# power_hub.net
KiCad netlist of a schematic drawn in EAGLE
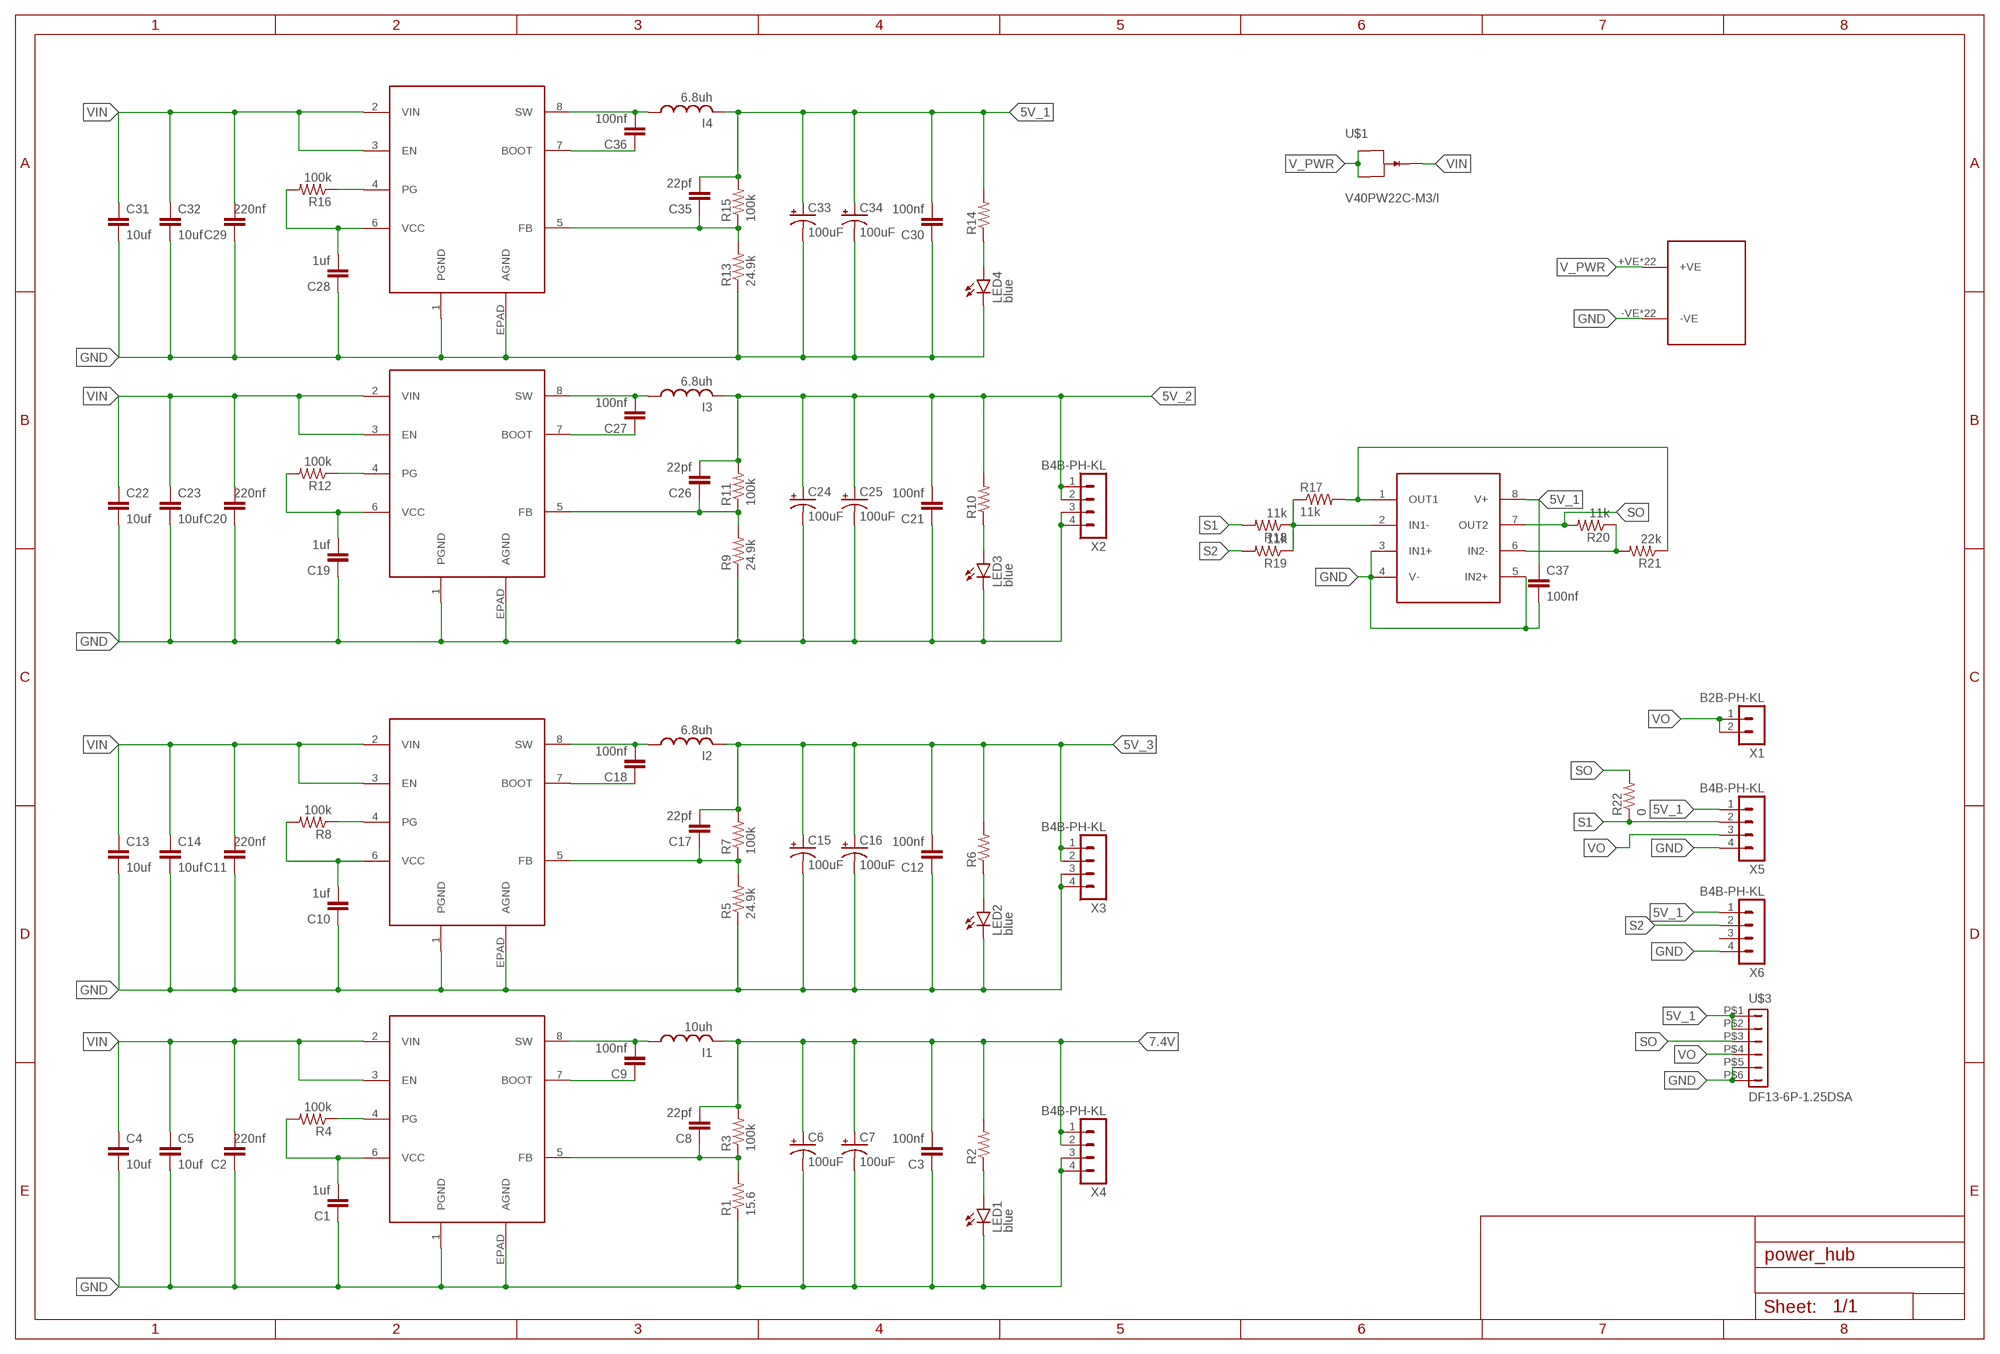
[diagram p0: schematic, sheet 1]

(export (version "E")
  (design (tool "Eeschema 10.0.6"))
  (components
    (comp (ref "C1")
      (value "1uf")
      (footprint "eagle-import:C0805")
      (libsource (lib "eagle-import") (part "C-EUC0805"))
    )
    (comp (ref "C2")
      (value "220nf")
      (footprint "eagle-import:C0805")
      (libsource (lib "eagle-import") (part "C-EUC0805"))
    )
    (comp (ref "C3")
      (value "100nf")
      (footprint "eagle-import:C0805")
      (libsource (lib "eagle-import") (part "C-EUC0805"))
    )
    (comp (ref "C4")
      (value "10uf")
      (footprint "eagle-import:C1210")
      (libsource (lib "eagle-import") (part "C-EUC1210"))
    )
    (comp (ref "C5")
      (value "10uf")
      (footprint "eagle-import:C1210")
      (libsource (lib "eagle-import") (part "C-EUC1210"))
    )
    (comp (ref "C6")
      (value "100uF")
      (footprint "eagle-import:PANASONIC_D")
      (libsource (lib "eagle-import") (part "100UF-POLAR-25V-20%(ELEC)"))
    )
    (comp (ref "C7")
      (value "100uF")
      (footprint "eagle-import:PANASONIC_D")
      (libsource (lib "eagle-import") (part "100UF-POLAR-25V-20%(ELEC)"))
    )
    (comp (ref "C8")
      (value "22pf")
      (footprint "eagle-import:C0805")
      (libsource (lib "eagle-import") (part "C-EUC0805"))
    )
    (comp (ref "C9")
      (value "100nf")
      (footprint "eagle-import:C0805")
      (libsource (lib "eagle-import") (part "C-EUC0805"))
    )
    (comp (ref "C10")
      (value "1uf")
      (footprint "eagle-import:C0805")
      (libsource (lib "eagle-import") (part "C-EUC0805"))
    )
    (comp (ref "C11")
      (value "220nf")
      (footprint "eagle-import:C0805")
      (libsource (lib "eagle-import") (part "C-EUC0805"))
    )
    (comp (ref "C12")
      (value "100nf")
      (footprint "eagle-import:C0805")
      (libsource (lib "eagle-import") (part "C-EUC0805"))
    )
    (comp (ref "C13")
      (value "10uf")
      (footprint "eagle-import:C1210")
      (libsource (lib "eagle-import") (part "C-EUC1210"))
    )
    (comp (ref "C14")
      (value "10uf")
      (footprint "eagle-import:C1210")
      (libsource (lib "eagle-import") (part "C-EUC1210"))
    )
    (comp (ref "C15")
      (value "100uF")
      (footprint "eagle-import:PANASONIC_D")
      (libsource (lib "eagle-import") (part "100UF-POLAR-25V-20%(ELEC)"))
    )
    (comp (ref "C16")
      (value "100uF")
      (footprint "eagle-import:PANASONIC_D")
      (libsource (lib "eagle-import") (part "100UF-POLAR-25V-20%(ELEC)"))
    )
    (comp (ref "C17")
      (value "22pf")
      (footprint "eagle-import:C0805")
      (libsource (lib "eagle-import") (part "C-EUC0805"))
    )
    (comp (ref "C18")
      (value "100nf")
      (footprint "eagle-import:C0805")
      (libsource (lib "eagle-import") (part "C-EUC0805"))
    )
    (comp (ref "C19")
      (value "1uf")
      (footprint "eagle-import:C0805")
      (libsource (lib "eagle-import") (part "C-EUC0805"))
    )
    (comp (ref "C20")
      (value "220nf")
      (footprint "eagle-import:C0805")
      (libsource (lib "eagle-import") (part "C-EUC0805"))
    )
    (comp (ref "C21")
      (value "100nf")
      (footprint "eagle-import:C0805")
      (libsource (lib "eagle-import") (part "C-EUC0805"))
    )
    (comp (ref "C22")
      (value "10uf")
      (footprint "eagle-import:C1210")
      (libsource (lib "eagle-import") (part "C-EUC1210"))
    )
    (comp (ref "C23")
      (value "10uf")
      (footprint "eagle-import:C1210")
      (libsource (lib "eagle-import") (part "C-EUC1210"))
    )
    (comp (ref "C24")
      (value "100uF")
      (footprint "eagle-import:PANASONIC_D")
      (libsource (lib "eagle-import") (part "100UF-POLAR-25V-20%(ELEC)"))
    )
    (comp (ref "C25")
      (value "100uF")
      (footprint "eagle-import:PANASONIC_D")
      (libsource (lib "eagle-import") (part "100UF-POLAR-25V-20%(ELEC)"))
    )
    (comp (ref "C26")
      (value "22pf")
      (footprint "eagle-import:C0805")
      (libsource (lib "eagle-import") (part "C-EUC0805"))
    )
    (comp (ref "C27")
      (value "100nf")
      (footprint "eagle-import:C0805")
      (libsource (lib "eagle-import") (part "C-EUC0805"))
    )
    (comp (ref "C28")
      (value "1uf")
      (footprint "eagle-import:C0805")
      (libsource (lib "eagle-import") (part "C-EUC0805"))
    )
    (comp (ref "C29")
      (value "220nf")
      (footprint "eagle-import:C0805")
      (libsource (lib "eagle-import") (part "C-EUC0805"))
    )
    (comp (ref "C30")
      (value "100nf")
      (footprint "eagle-import:C0805")
      (libsource (lib "eagle-import") (part "C-EUC0805"))
    )
    (comp (ref "C31")
      (value "10uf")
      (footprint "eagle-import:C1210")
      (libsource (lib "eagle-import") (part "C-EUC1210"))
    )
    (comp (ref "C32")
      (value "10uf")
      (footprint "eagle-import:C1210")
      (libsource (lib "eagle-import") (part "C-EUC1210"))
    )
    (comp (ref "C33")
      (value "100uF")
      (footprint "eagle-import:PANASONIC_D")
      (libsource (lib "eagle-import") (part "100UF-POLAR-25V-20%(ELEC)"))
    )
    (comp (ref "C34")
      (value "100uF")
      (footprint "eagle-import:PANASONIC_D")
      (libsource (lib "eagle-import") (part "100UF-POLAR-25V-20%(ELEC)"))
    )
    (comp (ref "C35")
      (value "22pf")
      (footprint "eagle-import:C0805")
      (libsource (lib "eagle-import") (part "C-EUC0805"))
    )
    (comp (ref "C36")
      (value "100nf")
      (footprint "eagle-import:C0805")
      (libsource (lib "eagle-import") (part "C-EUC0805"))
    )
    (comp (ref "C37")
      (value "100nf")
      (footprint "eagle-import:C0805")
      (libsource (lib "eagle-import") (part "C-EUC0805"))
    )
    (comp (ref "I1")
      (value "10uh")
      (footprint "eagle-import:INDUCTOR-1265")
      (libsource (lib "eagle-import") (part "INDUCTORINDUCTOR-1265"))
    )
    (comp (ref "I2")
      (value "6.8uh")
      (footprint "eagle-import:INDUCTOR-1265")
      (libsource (lib "eagle-import") (part "INDUCTORINDUCTOR-1265"))
    )
    (comp (ref "I3")
      (value "6.8uh")
      (footprint "eagle-import:INDUCTOR-1265")
      (libsource (lib "eagle-import") (part "INDUCTORINDUCTOR-1265"))
    )
    (comp (ref "I4")
      (value "6.8uh")
      (footprint "eagle-import:INDUCTOR-1265")
      (libsource (lib "eagle-import") (part "INDUCTORINDUCTOR-1265"))
    )
    (comp (ref "LED1")
      (value "blue")
      (footprint "eagle-import:CHIPLED_0805")
      (libsource (lib "eagle-import") (part "LEDCHIPLED_0805"))
    )
    (comp (ref "LED2")
      (value "blue")
      (footprint "eagle-import:CHIPLED_0805")
      (libsource (lib "eagle-import") (part "LEDCHIPLED_0805"))
    )
    (comp (ref "LED3")
      (value "blue")
      (footprint "eagle-import:CHIPLED_0805")
      (libsource (lib "eagle-import") (part "LEDCHIPLED_0805"))
    )
    (comp (ref "LED4")
      (value "blue")
      (footprint "eagle-import:CHIPLED_0805")
      (libsource (lib "eagle-import") (part "LEDCHIPLED_0805"))
    )
    (comp (ref "R1")
      (value "15.6")
      (footprint "eagle-import:R0805")
      (libsource (lib "eagle-import") (part "R-US_R0805"))
    )
    (comp (ref "R2")
      (value "1k")
      (footprint "eagle-import:R0805")
      (libsource (lib "eagle-import") (part "R-US_R0805"))
    )
    (comp (ref "R3")
      (value "100k")
      (footprint "eagle-import:R0805")
      (libsource (lib "eagle-import") (part "R-US_R0805"))
    )
    (comp (ref "R4")
      (value "100k")
      (footprint "eagle-import:R0805")
      (libsource (lib "eagle-import") (part "R-US_R0805"))
    )
    (comp (ref "R5")
      (value "24.9k")
      (footprint "eagle-import:R0805")
      (libsource (lib "eagle-import") (part "R-US_R0805"))
    )
    (comp (ref "R6")
      (value "1k")
      (footprint "eagle-import:R0805")
      (libsource (lib "eagle-import") (part "R-US_R0805"))
    )
    (comp (ref "R7")
      (value "100k")
      (footprint "eagle-import:R0805")
      (libsource (lib "eagle-import") (part "R-US_R0805"))
    )
    (comp (ref "R8")
      (value "100k")
      (footprint "eagle-import:R0805")
      (libsource (lib "eagle-import") (part "R-US_R0805"))
    )
    (comp (ref "R9")
      (value "24.9k")
      (footprint "eagle-import:R0805")
      (libsource (lib "eagle-import") (part "R-US_R0805"))
    )
    (comp (ref "R10")
      (value "1k")
      (footprint "eagle-import:R0805")
      (libsource (lib "eagle-import") (part "R-US_R0805"))
    )
    (comp (ref "R11")
      (value "100k")
      (footprint "eagle-import:R0805")
      (libsource (lib "eagle-import") (part "R-US_R0805"))
    )
    (comp (ref "R12")
      (value "100k")
      (footprint "eagle-import:R0805")
      (libsource (lib "eagle-import") (part "R-US_R0805"))
    )
    (comp (ref "R13")
      (value "24.9k")
      (footprint "eagle-import:R0805")
      (libsource (lib "eagle-import") (part "R-US_R0805"))
    )
    (comp (ref "R14")
      (value "1k")
      (footprint "eagle-import:R0805")
      (libsource (lib "eagle-import") (part "R-US_R0805"))
    )
    (comp (ref "R15")
      (value "100k")
      (footprint "eagle-import:R0805")
      (libsource (lib "eagle-import") (part "R-US_R0805"))
    )
    (comp (ref "R16")
      (value "100k")
      (footprint "eagle-import:R0805")
      (libsource (lib "eagle-import") (part "R-US_R0805"))
    )
    (comp (ref "R17")
      (value "11k")
      (footprint "eagle-import:R0805")
      (libsource (lib "eagle-import") (part "R-US_R0805"))
    )
    (comp (ref "R18")
      (value "11k")
      (footprint "eagle-import:R0805")
      (libsource (lib "eagle-import") (part "R-US_R0805"))
    )
    (comp (ref "R19")
      (value "11k")
      (footprint "eagle-import:R0805")
      (libsource (lib "eagle-import") (part "R-US_R0805"))
    )
    (comp (ref "R20")
      (value "11k")
      (footprint "eagle-import:R0805")
      (libsource (lib "eagle-import") (part "R-US_R0805"))
    )
    (comp (ref "R21")
      (value "22k")
      (footprint "eagle-import:R0805")
      (libsource (lib "eagle-import") (part "R-US_R0805"))
    )
    (comp (ref "R22")
      (value "0")
      (footprint "eagle-import:R0805")
      (libsource (lib "eagle-import") (part "R-US_R0805"))
    )
    (comp (ref "U$1")
      (value "V40PW22C-M3/I")
      (footprint "eagle-import:TO-252AE")
      (libsource (lib "eagle-import") (part "DIODE-TO252"))
    )
    (comp (ref "U$2")
      (value "LM3588")
      (footprint "eagle-import:SOP-08")
      (libsource (lib "eagle-import") (part "LM3588"))
    )
    (comp (ref "U$3")
      (value "DF13-6P-1.25DSA")
      (footprint "eagle-import:DF13-6P-1.25DSA")
      (libsource (lib "eagle-import") (part "DF13-6P-1.25DSA"))
    )
    (comp (ref "U$4")
      (value "CON_PAD")
      (footprint "eagle-import:MOTOR_PAD")
      (libsource (lib "eagle-import") (part "CON_PAD"))
    )
    (comp (ref "U1")
      (value "LMR33640")
      (footprint "eagle-import:SO-POWERPAD8_DDA_TEX-M")
      (libsource (lib "eagle-import") (part "LMR33640"))
    )
    (comp (ref "U2")
      (value "LMR33640")
      (footprint "eagle-import:SO-POWERPAD8_DDA_TEX-M")
      (libsource (lib "eagle-import") (part "LMR33640"))
    )
    (comp (ref "U3")
      (value "LMR33640")
      (footprint "eagle-import:SO-POWERPAD8_DDA_TEX-M")
      (libsource (lib "eagle-import") (part "LMR33640"))
    )
    (comp (ref "U4")
      (value "LMR33640")
      (footprint "eagle-import:SO-POWERPAD8_DDA_TEX-M")
      (libsource (lib "eagle-import") (part "LMR33640"))
    )
    (comp (ref "X1")
      (value "B2B-PH-KL")
      (footprint "eagle-import:B2B-PH-K-S")
      (libsource (lib "eagle-import") (part "B2B-PH-KL"))
    )
    (comp (ref "X2")
      (value "B4B-PH-KL")
      (footprint "eagle-import:B4B-PH-K-S")
      (libsource (lib "eagle-import") (part "B4B-PH-KL"))
    )
    (comp (ref "X3")
      (value "B4B-PH-KL")
      (footprint "eagle-import:B4B-PH-K-S")
      (libsource (lib "eagle-import") (part "B4B-PH-KL"))
    )
    (comp (ref "X4")
      (value "B4B-PH-KL")
      (footprint "eagle-import:B4B-PH-K-S")
      (libsource (lib "eagle-import") (part "B4B-PH-KL"))
    )
    (comp (ref "X5")
      (value "B4B-PH-KL")
      (footprint "eagle-import:B4B-PH-K-S")
      (libsource (lib "eagle-import") (part "B4B-PH-KL"))
    )
    (comp (ref "X6")
      (value "B4B-PH-KL")
      (footprint "eagle-import:B4B-PH-K-S")
      (libsource (lib "eagle-import") (part "B4B-PH-KL"))
    )
  )
  (nets
    (net (code "1") (name "5V_1") (class "Default")
      (node (ref "C30") (pin "2") (pinfunction "2_2") (pintype "passive"))
      (node (ref "C33") (pin "+") (pinfunction "+_+") (pintype "passive"))
      (node (ref "C34") (pin "+") (pinfunction "+_+") (pintype "passive"))
      (node (ref "C35") (pin "2") (pinfunction "2_2") (pintype "passive"))
      (node (ref "C37") (pin "1") (pinfunction "1_1") (pintype "passive"))
      (node (ref "I4") (pin "P$2") (pinfunction "2_P$2") (pintype "passive"))
      (node (ref "R14") (pin "2") (pinfunction "2_2") (pintype "passive"))
      (node (ref "R15") (pin "2") (pinfunction "2_2") (pintype "passive"))
      (node (ref "U$2") (pin "8") (pinfunction "V+_8") (pintype "bidirectional"))
      (node (ref "U$3") (pin "P$1") (pinfunction "1_P$1") (pintype "passive"))
      (node (ref "U$3") (pin "P$2") (pinfunction "2_P$2") (pintype "passive"))
      (node (ref "X5") (pin "1") (pinfunction "1_1") (pintype "passive"))
      (node (ref "X6") (pin "1") (pinfunction "1_1") (pintype "passive"))
    )
    (net (code "2") (name "5V_2") (class "Default")
      (node (ref "C21") (pin "2") (pinfunction "2_2") (pintype "passive"))
      (node (ref "C24") (pin "+") (pinfunction "+_+") (pintype "passive"))
      (node (ref "C25") (pin "+") (pinfunction "+_+") (pintype "passive"))
      (node (ref "C26") (pin "2") (pinfunction "2_2") (pintype "passive"))
      (node (ref "I3") (pin "P$2") (pinfunction "2_P$2") (pintype "passive"))
      (node (ref "R10") (pin "2") (pinfunction "2_2") (pintype "passive"))
      (node (ref "R11") (pin "2") (pinfunction "2_2") (pintype "passive"))
      (node (ref "X2") (pin "1") (pinfunction "1_1") (pintype "passive"))
      (node (ref "X2") (pin "2") (pinfunction "2_2") (pintype "passive"))
    )
    (net (code "3") (name "5V_3") (class "Default")
      (node (ref "C12") (pin "2") (pinfunction "2_2") (pintype "passive"))
      (node (ref "C15") (pin "+") (pinfunction "+_+") (pintype "passive"))
      (node (ref "C16") (pin "+") (pinfunction "+_+") (pintype "passive"))
      (node (ref "C17") (pin "2") (pinfunction "2_2") (pintype "passive"))
      (node (ref "I2") (pin "P$2") (pinfunction "2_P$2") (pintype "passive"))
      (node (ref "R6") (pin "2") (pinfunction "2_2") (pintype "passive"))
      (node (ref "R7") (pin "2") (pinfunction "2_2") (pintype "passive"))
      (node (ref "X3") (pin "1") (pinfunction "1_1") (pintype "passive"))
      (node (ref "X3") (pin "2") (pinfunction "2_2") (pintype "passive"))
    )
    (net (code "4") (name "7.4V") (class "Default")
      (node (ref "C3") (pin "2") (pinfunction "2_2") (pintype "passive"))
      (node (ref "C6") (pin "+") (pinfunction "+_+") (pintype "passive"))
      (node (ref "C7") (pin "+") (pinfunction "+_+") (pintype "passive"))
      (node (ref "C8") (pin "2") (pinfunction "2_2") (pintype "passive"))
      (node (ref "I1") (pin "P$2") (pinfunction "2_P$2") (pintype "passive"))
      (node (ref "R2") (pin "2") (pinfunction "2_2") (pintype "passive"))
      (node (ref "R3") (pin "2") (pinfunction "2_2") (pintype "passive"))
      (node (ref "X4") (pin "1") (pinfunction "1_1") (pintype "passive"))
      (node (ref "X4") (pin "2") (pinfunction "2_2") (pintype "passive"))
    )
    (net (code "5") (name "GND") (class "Default")
      (node (ref "C1") (pin "1") (pinfunction "1_1") (pintype "passive"))
      (node (ref "C10") (pin "1") (pinfunction "1_1") (pintype "passive"))
      (node (ref "C11") (pin "1") (pinfunction "1_1") (pintype "passive"))
      (node (ref "C12") (pin "1") (pinfunction "1_1") (pintype "passive"))
      (node (ref "C13") (pin "2") (pinfunction "2_2") (pintype "passive"))
      (node (ref "C14") (pin "2") (pinfunction "2_2") (pintype "passive"))
      (node (ref "C15") (pin "-") (pinfunction "-_-") (pintype "passive"))
      (node (ref "C16") (pin "-") (pinfunction "-_-") (pintype "passive"))
      (node (ref "C19") (pin "1") (pinfunction "1_1") (pintype "passive"))
      (node (ref "C2") (pin "1") (pinfunction "1_1") (pintype "passive"))
      (node (ref "C20") (pin "1") (pinfunction "1_1") (pintype "passive"))
      (node (ref "C21") (pin "1") (pinfunction "1_1") (pintype "passive"))
      (node (ref "C22") (pin "2") (pinfunction "2_2") (pintype "passive"))
      (node (ref "C23") (pin "2") (pinfunction "2_2") (pintype "passive"))
      (node (ref "C24") (pin "-") (pinfunction "-_-") (pintype "passive"))
      (node (ref "C25") (pin "-") (pinfunction "-_-") (pintype "passive"))
      (node (ref "C28") (pin "1") (pinfunction "1_1") (pintype "passive"))
      (node (ref "C29") (pin "1") (pinfunction "1_1") (pintype "passive"))
      (node (ref "C3") (pin "1") (pinfunction "1_1") (pintype "passive"))
      (node (ref "C30") (pin "1") (pinfunction "1_1") (pintype "passive"))
      (node (ref "C31") (pin "2") (pinfunction "2_2") (pintype "passive"))
      (node (ref "C32") (pin "2") (pinfunction "2_2") (pintype "passive"))
      (node (ref "C33") (pin "-") (pinfunction "-_-") (pintype "passive"))
      (node (ref "C34") (pin "-") (pinfunction "-_-") (pintype "passive"))
      (node (ref "C37") (pin "2") (pinfunction "2_2") (pintype "passive"))
      (node (ref "C4") (pin "2") (pinfunction "2_2") (pintype "passive"))
      (node (ref "C5") (pin "2") (pinfunction "2_2") (pintype "passive"))
      (node (ref "C6") (pin "-") (pinfunction "-_-") (pintype "passive"))
      (node (ref "C7") (pin "-") (pinfunction "-_-") (pintype "passive"))
      (node (ref "LED1") (pin "C") (pinfunction "C_C") (pintype "passive"))
      (node (ref "LED2") (pin "C") (pinfunction "C_C") (pintype "passive"))
      (node (ref "LED3") (pin "C") (pinfunction "C_C") (pintype "passive"))
      (node (ref "LED4") (pin "C") (pinfunction "C_C") (pintype "passive"))
      (node (ref "R1") (pin "1") (pinfunction "1_1") (pintype "passive"))
      (node (ref "R13") (pin "1") (pinfunction "1_1") (pintype "passive"))
      (node (ref "R5") (pin "1") (pinfunction "1_1") (pintype "passive"))
      (node (ref "R9") (pin "1") (pinfunction "1_1") (pintype "passive"))
      (node (ref "U$2") (pin "3") (pinfunction "IN1+_3") (pintype "bidirectional"))
      (node (ref "U$2") (pin "4") (pinfunction "V-_4") (pintype "bidirectional"))
      (node (ref "U$2") (pin "5") (pinfunction "IN2+_5") (pintype "bidirectional"))
      (node (ref "U$3") (pin "P$5") (pinfunction "5_P$5") (pintype "passive"))
      (node (ref "U$3") (pin "P$6") (pinfunction "6_P$6") (pintype "passive"))
      (node (ref "U$4") (pin "-VE") (pinfunction "-VE_-VE") (pintype "output"))
      (node (ref "U$4") (pin "-VE_1") (pinfunction "-VE_-VE_1") (pintype "output"))
      (node (ref "U$4") (pin "V37") (pinfunction "-VE_V37") (pintype "output"))
      (node (ref "U$4") (pin "V38") (pinfunction "-VE_V38") (pintype "output"))
      (node (ref "U$4") (pin "V39") (pinfunction "-VE_V39") (pintype "output"))
      (node (ref "U$4") (pin "V40") (pinfunction "-VE_V40") (pintype "output"))
      (node (ref "U$4") (pin "V41") (pinfunction "-VE_V41") (pintype "output"))
      (node (ref "U$4") (pin "V42") (pinfunction "-VE_V42") (pintype "output"))
      (node (ref "U$4") (pin "V43") (pinfunction "-VE_V43") (pintype "output"))
      (node (ref "U$4") (pin "V44") (pinfunction "-VE_V44") (pintype "output"))
      (node (ref "U$4") (pin "V45") (pinfunction "-VE_V45") (pintype "output"))
      (node (ref "U$4") (pin "V46") (pinfunction "-VE_V46") (pintype "output"))
      (node (ref "U$4") (pin "V47") (pinfunction "-VE_V47") (pintype "output"))
      (node (ref "U$4") (pin "V48") (pinfunction "-VE_V48") (pintype "output"))
      (node (ref "U$4") (pin "V49") (pinfunction "-VE_V49") (pintype "output"))
      (node (ref "U$4") (pin "V50") (pinfunction "-VE_V50") (pintype "output"))
      (node (ref "U$4") (pin "V51") (pinfunction "-VE_V51") (pintype "output"))
      (node (ref "U$4") (pin "V52") (pinfunction "-VE_V52") (pintype "output"))
      (node (ref "U$4") (pin "V53") (pinfunction "-VE_V53") (pintype "output"))
      (node (ref "U$4") (pin "V54") (pinfunction "-VE_V54") (pintype "output"))
      (node (ref "U$4") (pin "V55") (pinfunction "-VE_V55") (pintype "output"))
      (node (ref "U$4") (pin "V56") (pinfunction "-VE_V56") (pintype "output"))
      (node (ref "U1") (pin "1") (pinfunction "PGND_1") (pintype "bidirectional"))
      (node (ref "U1") (pin "EPAD") (pinfunction "AGND_EPAD") (pintype "bidirectional"))
      (node (ref "U2") (pin "1") (pinfunction "PGND_1") (pintype "bidirectional"))
      (node (ref "U2") (pin "EPAD") (pinfunction "AGND_EPAD") (pintype "bidirectional"))
      (node (ref "U3") (pin "1") (pinfunction "PGND_1") (pintype "bidirectional"))
      (node (ref "U3") (pin "EPAD") (pinfunction "AGND_EPAD") (pintype "bidirectional"))
      (node (ref "U4") (pin "1") (pinfunction "PGND_1") (pintype "bidirectional"))
      (node (ref "U4") (pin "EPAD") (pinfunction "AGND_EPAD") (pintype "bidirectional"))
      (node (ref "X2") (pin "3") (pinfunction "3_3") (pintype "passive"))
      (node (ref "X2") (pin "4") (pinfunction "4_4") (pintype "passive"))
      (node (ref "X3") (pin "3") (pinfunction "3_3") (pintype "passive"))
      (node (ref "X3") (pin "4") (pinfunction "4_4") (pintype "passive"))
      (node (ref "X4") (pin "3") (pinfunction "3_3") (pintype "passive"))
      (node (ref "X4") (pin "4") (pinfunction "4_4") (pintype "passive"))
      (node (ref "X5") (pin "4") (pinfunction "4_4") (pintype "passive"))
      (node (ref "X6") (pin "4") (pinfunction "4_4") (pintype "passive"))
    )
    (net (code "6") (name "Net-(I1-1)") (class "Default")
      (node (ref "C9") (pin "2") (pinfunction "2_2") (pintype "passive"))
      (node (ref "I1") (pin "P$1") (pinfunction "1_P$1") (pintype "passive"))
      (node (ref "U1") (pin "8") (pinfunction "SW_8") (pintype "bidirectional"))
    )
    (net (code "7") (name "Net-(I2-1)") (class "Default")
      (node (ref "C18") (pin "2") (pinfunction "2_2") (pintype "passive"))
      (node (ref "I2") (pin "P$1") (pinfunction "1_P$1") (pintype "passive"))
      (node (ref "U2") (pin "8") (pinfunction "SW_8") (pintype "bidirectional"))
    )
    (net (code "8") (name "Net-(I3-1)") (class "Default")
      (node (ref "C27") (pin "2") (pinfunction "2_2") (pintype "passive"))
      (node (ref "I3") (pin "P$1") (pinfunction "1_P$1") (pintype "passive"))
      (node (ref "U3") (pin "8") (pinfunction "SW_8") (pintype "bidirectional"))
    )
    (net (code "9") (name "Net-(I4-1)") (class "Default")
      (node (ref "C36") (pin "2") (pinfunction "2_2") (pintype "passive"))
      (node (ref "I4") (pin "P$1") (pinfunction "1_P$1") (pintype "passive"))
      (node (ref "U4") (pin "8") (pinfunction "SW_8") (pintype "bidirectional"))
    )
    (net (code "10") (name "Net-(LED1-PadA)") (class "Default")
      (node (ref "LED1") (pin "A") (pinfunction "A_A") (pintype "passive"))
      (node (ref "R2") (pin "1") (pinfunction "1_1") (pintype "passive"))
    )
    (net (code "11") (name "Net-(LED2-PadA)") (class "Default")
      (node (ref "LED2") (pin "A") (pinfunction "A_A") (pintype "passive"))
      (node (ref "R6") (pin "1") (pinfunction "1_1") (pintype "passive"))
    )
    (net (code "12") (name "Net-(LED3-PadA)") (class "Default")
      (node (ref "LED3") (pin "A") (pinfunction "A_A") (pintype "passive"))
      (node (ref "R10") (pin "1") (pinfunction "1_1") (pintype "passive"))
    )
    (net (code "13") (name "Net-(LED4-PadA)") (class "Default")
      (node (ref "LED4") (pin "A") (pinfunction "A_A") (pintype "passive"))
      (node (ref "R14") (pin "1") (pinfunction "1_1") (pintype "passive"))
    )
    (net (code "14") (name "Net-(U$2-IN1-)") (class "Default")
      (node (ref "R17") (pin "1") (pinfunction "1_1") (pintype "passive"))
      (node (ref "R18") (pin "1") (pinfunction "1_1") (pintype "passive"))
      (node (ref "R19") (pin "1") (pinfunction "1_1") (pintype "passive"))
      (node (ref "U$2") (pin "2") (pinfunction "IN1-_2") (pintype "bidirectional"))
    )
    (net (code "15") (name "Net-(U$2-IN2-)") (class "Default")
      (node (ref "R20") (pin "1") (pinfunction "1_1") (pintype "passive"))
      (node (ref "R21") (pin "2") (pinfunction "2_2") (pintype "passive"))
      (node (ref "U$2") (pin "6") (pinfunction "IN2-_6") (pintype "bidirectional"))
    )
    (net (code "16") (name "Net-(U$2-OUT1)") (class "Default")
      (node (ref "R17") (pin "2") (pinfunction "2_2") (pintype "passive"))
      (node (ref "R21") (pin "1") (pinfunction "1_1") (pintype "passive"))
      (node (ref "U$2") (pin "1") (pinfunction "OUT1_1") (pintype "bidirectional"))
    )
    (net (code "17") (name "Net-(U1-BOOT)") (class "Default")
      (node (ref "C9") (pin "1") (pinfunction "1_1") (pintype "passive"))
      (node (ref "U1") (pin "7") (pinfunction "BOOT_7") (pintype "bidirectional"))
    )
    (net (code "18") (name "Net-(U1-FB)") (class "Default")
      (node (ref "C8") (pin "1") (pinfunction "1_1") (pintype "passive"))
      (node (ref "R1") (pin "2") (pinfunction "2_2") (pintype "passive"))
      (node (ref "R3") (pin "1") (pinfunction "1_1") (pintype "passive"))
      (node (ref "U1") (pin "5") (pinfunction "FB_5") (pintype "bidirectional"))
    )
    (net (code "19") (name "Net-(U1-PG)") (class "Default")
      (node (ref "R4") (pin "1") (pinfunction "1_1") (pintype "passive"))
      (node (ref "U1") (pin "4") (pinfunction "PG_4") (pintype "bidirectional"))
    )
    (net (code "20") (name "Net-(U1-VCC)") (class "Default")
      (node (ref "C1") (pin "2") (pinfunction "2_2") (pintype "passive"))
      (node (ref "R4") (pin "2") (pinfunction "2_2") (pintype "passive"))
      (node (ref "U1") (pin "6") (pinfunction "VCC_6") (pintype "bidirectional"))
    )
    (net (code "21") (name "Net-(U2-BOOT)") (class "Default")
      (node (ref "C18") (pin "1") (pinfunction "1_1") (pintype "passive"))
      (node (ref "U2") (pin "7") (pinfunction "BOOT_7") (pintype "bidirectional"))
    )
    (net (code "22") (name "Net-(U2-FB)") (class "Default")
      (node (ref "C17") (pin "1") (pinfunction "1_1") (pintype "passive"))
      (node (ref "R5") (pin "2") (pinfunction "2_2") (pintype "passive"))
      (node (ref "R7") (pin "1") (pinfunction "1_1") (pintype "passive"))
      (node (ref "U2") (pin "5") (pinfunction "FB_5") (pintype "bidirectional"))
    )
    (net (code "23") (name "Net-(U2-PG)") (class "Default")
      (node (ref "R8") (pin "1") (pinfunction "1_1") (pintype "passive"))
      (node (ref "U2") (pin "4") (pinfunction "PG_4") (pintype "bidirectional"))
    )
    (net (code "24") (name "Net-(U2-VCC)") (class "Default")
      (node (ref "C10") (pin "2") (pinfunction "2_2") (pintype "passive"))
      (node (ref "R8") (pin "2") (pinfunction "2_2") (pintype "passive"))
      (node (ref "U2") (pin "6") (pinfunction "VCC_6") (pintype "bidirectional"))
    )
    (net (code "25") (name "Net-(U3-BOOT)") (class "Default")
      (node (ref "C27") (pin "1") (pinfunction "1_1") (pintype "passive"))
      (node (ref "U3") (pin "7") (pinfunction "BOOT_7") (pintype "bidirectional"))
    )
    (net (code "26") (name "Net-(U3-FB)") (class "Default")
      (node (ref "C26") (pin "1") (pinfunction "1_1") (pintype "passive"))
      (node (ref "R11") (pin "1") (pinfunction "1_1") (pintype "passive"))
      (node (ref "R9") (pin "2") (pinfunction "2_2") (pintype "passive"))
      (node (ref "U3") (pin "5") (pinfunction "FB_5") (pintype "bidirectional"))
    )
    (net (code "27") (name "Net-(U3-PG)") (class "Default")
      (node (ref "R12") (pin "1") (pinfunction "1_1") (pintype "passive"))
      (node (ref "U3") (pin "4") (pinfunction "PG_4") (pintype "bidirectional"))
    )
    (net (code "28") (name "Net-(U3-VCC)") (class "Default")
      (node (ref "C19") (pin "2") (pinfunction "2_2") (pintype "passive"))
      (node (ref "R12") (pin "2") (pinfunction "2_2") (pintype "passive"))
      (node (ref "U3") (pin "6") (pinfunction "VCC_6") (pintype "bidirectional"))
    )
    (net (code "29") (name "Net-(U4-BOOT)") (class "Default")
      (node (ref "C36") (pin "1") (pinfunction "1_1") (pintype "passive"))
      (node (ref "U4") (pin "7") (pinfunction "BOOT_7") (pintype "bidirectional"))
    )
    (net (code "30") (name "Net-(U4-FB)") (class "Default")
      (node (ref "C35") (pin "1") (pinfunction "1_1") (pintype "passive"))
      (node (ref "R13") (pin "2") (pinfunction "2_2") (pintype "passive"))
      (node (ref "R15") (pin "1") (pinfunction "1_1") (pintype "passive"))
      (node (ref "U4") (pin "5") (pinfunction "FB_5") (pintype "bidirectional"))
    )
    (net (code "31") (name "Net-(U4-PG)") (class "Default")
      (node (ref "R16") (pin "1") (pinfunction "1_1") (pintype "passive"))
      (node (ref "U4") (pin "4") (pinfunction "PG_4") (pintype "bidirectional"))
    )
    (net (code "32") (name "Net-(U4-VCC)") (class "Default")
      (node (ref "C28") (pin "2") (pinfunction "2_2") (pintype "passive"))
      (node (ref "R16") (pin "2") (pinfunction "2_2") (pintype "passive"))
      (node (ref "U4") (pin "6") (pinfunction "VCC_6") (pintype "bidirectional"))
    )
    (net (code "33") (name "S1") (class "Default")
      (node (ref "R18") (pin "2") (pinfunction "2_2") (pintype "passive"))
      (node (ref "R22") (pin "1") (pinfunction "1_1") (pintype "passive"))
      (node (ref "X5") (pin "2") (pinfunction "2_2") (pintype "passive"))
    )
    (net (code "34") (name "S2") (class "Default")
      (node (ref "R19") (pin "2") (pinfunction "2_2") (pintype "passive"))
      (node (ref "X6") (pin "2") (pinfunction "2_2") (pintype "passive"))
    )
    (net (code "35") (name "SO") (class "Default")
      (node (ref "R20") (pin "2") (pinfunction "2_2") (pintype "passive"))
      (node (ref "R22") (pin "2") (pinfunction "2_2") (pintype "passive"))
      (node (ref "U$2") (pin "7") (pinfunction "OUT2_7") (pintype "bidirectional"))
      (node (ref "U$3") (pin "P$3") (pinfunction "3_P$3") (pintype "passive"))
    )
    (net (code "36") (name "VIN") (class "Default")
      (node (ref "C11") (pin "2") (pinfunction "2_2") (pintype "passive"))
      (node (ref "C13") (pin "1") (pinfunction "1_1") (pintype "passive"))
      (node (ref "C14") (pin "1") (pinfunction "1_1") (pintype "passive"))
      (node (ref "C2") (pin "2") (pinfunction "2_2") (pintype "passive"))
      (node (ref "C20") (pin "2") (pinfunction "2_2") (pintype "passive"))
      (node (ref "C22") (pin "1") (pinfunction "1_1") (pintype "passive"))
      (node (ref "C23") (pin "1") (pinfunction "1_1") (pintype "passive"))
      (node (ref "C29") (pin "2") (pinfunction "2_2") (pintype "passive"))
      (node (ref "C31") (pin "1") (pinfunction "1_1") (pintype "passive"))
      (node (ref "C32") (pin "1") (pinfunction "1_1") (pintype "passive"))
      (node (ref "C4") (pin "1") (pinfunction "1_1") (pintype "passive"))
      (node (ref "C5") (pin "1") (pinfunction "1_1") (pintype "passive"))
      (node (ref "U$1") (pin "P$1") (pinfunction "K_P$1") (pintype "passive"))
      (node (ref "U1") (pin "2") (pinfunction "VIN_2") (pintype "bidirectional"))
      (node (ref "U1") (pin "3") (pinfunction "EN_3") (pintype "bidirectional"))
      (node (ref "U2") (pin "2") (pinfunction "VIN_2") (pintype "bidirectional"))
      (node (ref "U2") (pin "3") (pinfunction "EN_3") (pintype "bidirectional"))
      (node (ref "U3") (pin "2") (pinfunction "VIN_2") (pintype "bidirectional"))
      (node (ref "U3") (pin "3") (pinfunction "EN_3") (pintype "bidirectional"))
      (node (ref "U4") (pin "2") (pinfunction "VIN_2") (pintype "bidirectional"))
      (node (ref "U4") (pin "3") (pinfunction "EN_3") (pintype "bidirectional"))
    )
    (net (code "37") (name "VO") (class "Default")
      (node (ref "U$3") (pin "P$4") (pinfunction "4_P$4") (pintype "passive"))
      (node (ref "X1") (pin "1") (pinfunction "1_1") (pintype "passive"))
      (node (ref "X1") (pin "2") (pinfunction "2_2") (pintype "passive"))
      (node (ref "X5") (pin "3") (pinfunction "3_3") (pintype "passive"))
    )
    (net (code "38") (name "V_PWR") (class "Default")
      (node (ref "U$1") (pin "P$2") (pinfunction "A1_P$2") (pintype "passive"))
      (node (ref "U$1") (pin "P$3") (pinfunction "A2_P$3") (pintype "passive"))
      (node (ref "U$4") (pin "+VE") (pinfunction "+VE_+VE") (pintype "output"))
      (node (ref "U$4") (pin "+VE_1") (pinfunction "+VE_+VE_1") (pintype "output"))
      (node (ref "U$4") (pin "V10") (pinfunction "+VE_V10") (pintype "output"))
      (node (ref "U$4") (pin "V11") (pinfunction "+VE_V11") (pintype "output"))
      (node (ref "U$4") (pin "V12") (pinfunction "+VE_V12") (pintype "output"))
      (node (ref "U$4") (pin "V13") (pinfunction "+VE_V13") (pintype "output"))
      (node (ref "U$4") (pin "V14") (pinfunction "+VE_V14") (pintype "output"))
      (node (ref "U$4") (pin "V15") (pinfunction "+VE_V15") (pintype "output"))
      (node (ref "U$4") (pin "V16") (pinfunction "+VE_V16") (pintype "output"))
      (node (ref "U$4") (pin "V17") (pinfunction "+VE_V17") (pintype "output"))
      (node (ref "U$4") (pin "V18") (pinfunction "+VE_V18") (pintype "output"))
      (node (ref "U$4") (pin "V19") (pinfunction "+VE_V19") (pintype "output"))
      (node (ref "U$4") (pin "V20") (pinfunction "+VE_V20") (pintype "output"))
      (node (ref "U$4") (pin "V21") (pinfunction "+VE_V21") (pintype "output"))
      (node (ref "U$4") (pin "V22") (pinfunction "+VE_V22") (pintype "output"))
      (node (ref "U$4") (pin "V23") (pinfunction "+VE_V23") (pintype "output"))
      (node (ref "U$4") (pin "V24") (pinfunction "+VE_V24") (pintype "output"))
      (node (ref "U$4") (pin "V25") (pinfunction "+VE_V25") (pintype "output"))
      (node (ref "U$4") (pin "V26") (pinfunction "+VE_V26") (pintype "output"))
      (node (ref "U$4") (pin "V7") (pinfunction "+VE_V7") (pintype "output"))
      (node (ref "U$4") (pin "V8") (pinfunction "+VE_V8") (pintype "output"))
      (node (ref "U$4") (pin "V9") (pinfunction "+VE_V9") (pintype "output"))
    )
    (net (code "39") (name "unconnected-(X6-Pad3)") (class "Default")
      (node (ref "X6") (pin "3") (pinfunction "3_3") (pintype "passive"))
    )
  )
)
